# UART.net
KiCad netlist of a schematic drawn in Altium Designer
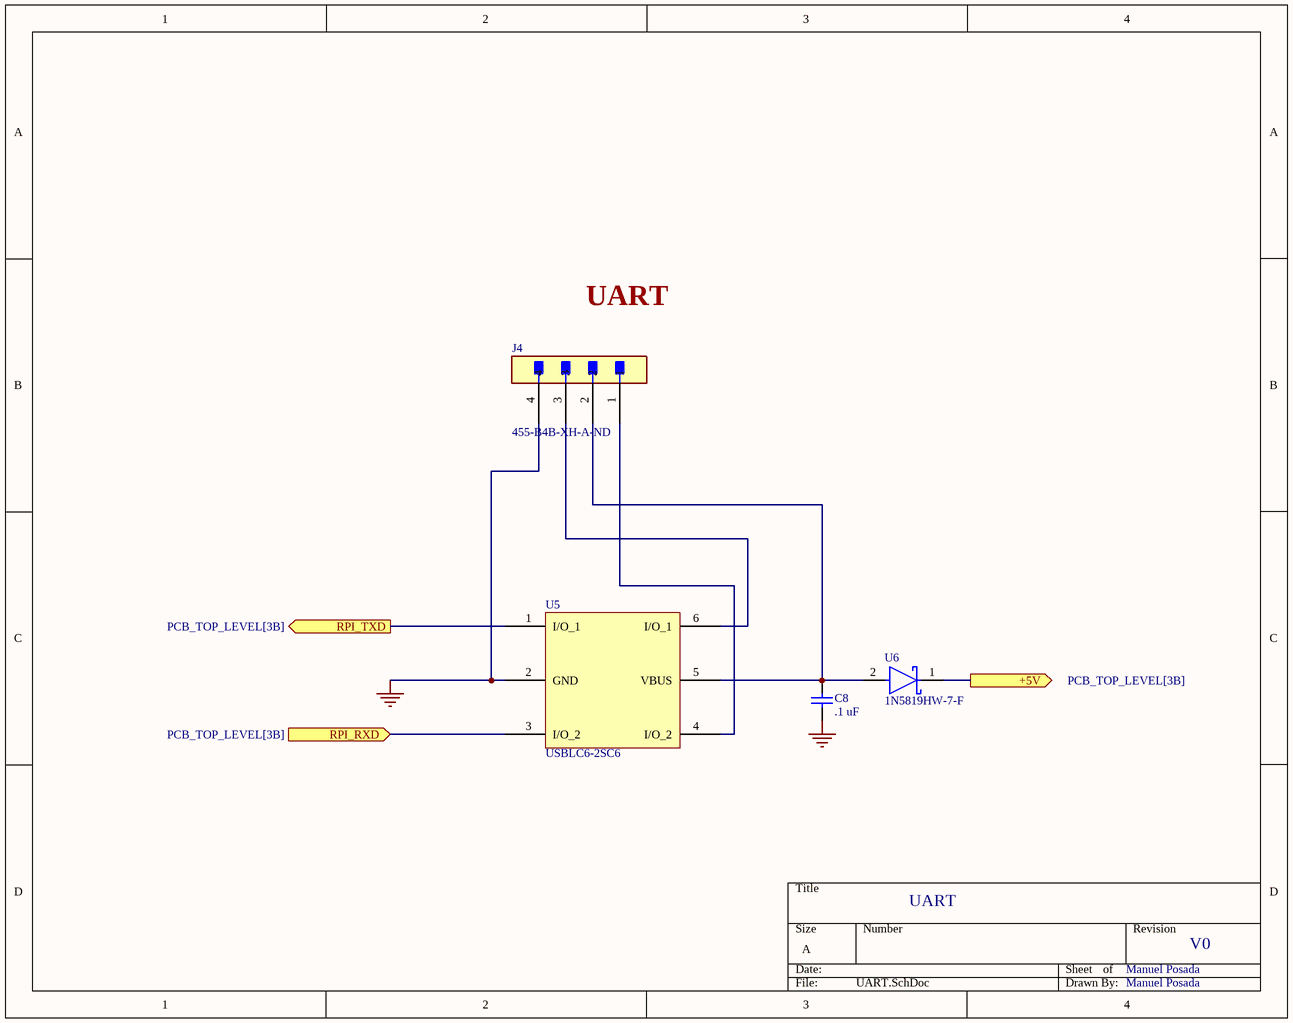
[diagram p0: UART.SchDoc]

(export (version "E")
  (design (tool "Eeschema 10.0.6"))
  (components
    (comp (ref "C8")
      (value ".1 uF")
      (footprint "CAP_CL21_SAM-L")
      (description "50V 100nF X7R ±10% 0805 Multilayer Ceramic Capacitors MLCC - SMD/SMT ROHS")
      (fields
        (field (name "MANUFACTURER") "Samsung Electro-Mechanics")
        (field (name "MANUFACTURER PART NUMBER") "CL21B104KBCNNNC")
      )
      (libsource (lib "Schlib") (part "CL21B104KBCNNNC"))
    )
    (comp (ref "J4")
      (value "455-B4B-XH-A-ND")
      (footprint "CONN_B4B-XH-A_JST")
      (description "Board Connector, 4 Contact(s), 1 Row(s), Male, Straight, Solder Terminal")
      (fields (field (name "MANUFACTURER") "JST") (field (name "MANUFACTURER PART NUMBER") "B4B-XH-A"))
      (libsource (lib "Schlib") (part "B4B-XH-A"))
    )
    (comp (ref "U5")
      (value "USBLC6-2SC6")
      (footprint "SOT23-6L_STM")
      (description "17V Clamp 5A (8/20µs) Ipp Tvs Diode Surface Mount SOT-23-6")
      (fields (field (name "MANUFACTURER") "STMicroelectronics"))
      (libsource (lib "Schlib") (part "USBLC6-2SC6"))
    )
    (comp (ref "U6")
      (value "1N5819HW-7-F")
      (footprint "FP-SOD123-IPC_B")
      (description "DIODE SCHOTTKY 40V 1A SOD123")
      (fields (field (name "MANUFACTURER") "Diodes Inc."))
      (libsource (lib "Schlib") (part "1N5819HW-7-F"))
    )
  )
  (nets
    (net (code "1") (name "/+5V") (class "Default")
      (node (ref "U6") (pin "1") (pinfunction "C_1") (pintype "passive"))
    )
    (net (code "2") (name "/RPI_RXD") (class "Default")
      (node (ref "U5") (pin "3") (pinfunction "I/O_2_3") (pintype "passive"))
    )
    (net (code "3") (name "/RPI_TXD") (class "Default")
      (node (ref "U5") (pin "1") (pinfunction "I/O_1_1") (pintype "passive"))
    )
    (net (code "4") (name "GND") (class "Default")
      (node (ref "C8") (pin "1") (pinfunction "1_1") (pintype "passive"))
      (node (ref "J4") (pin "4") (pinfunction "4_4") (pintype "passive"))
      (node (ref "U5") (pin "2") (pinfunction "GND_2") (pintype "passive"))
    )
    (net (code "5") (name "Net-(J4-Pad1)") (class "Default")
      (node (ref "J4") (pin "1") (pinfunction "1_1") (pintype "passive"))
      (node (ref "U5") (pin "4") (pinfunction "I/O_2_4") (pintype "passive"))
    )
    (net (code "6") (name "Net-(J4-Pad3)") (class "Default")
      (node (ref "J4") (pin "3") (pinfunction "3_3") (pintype "passive"))
      (node (ref "U5") (pin "6") (pinfunction "I/O_1_6") (pintype "passive"))
    )
    (net (code "7") (name "Net-(U5-VBUS)") (class "Default")
      (node (ref "C8") (pin "2") (pinfunction "2_2") (pintype "passive"))
      (node (ref "J4") (pin "2") (pinfunction "2_2") (pintype "passive"))
      (node (ref "U5") (pin "5") (pinfunction "VBUS_5") (pintype "passive"))
      (node (ref "U6") (pin "2") (pinfunction "A_2") (pintype "passive"))
    )
  )
)
